# USBC-DEV-2_0.net
KiCad netlist of a schematic drawn in Altium Designer
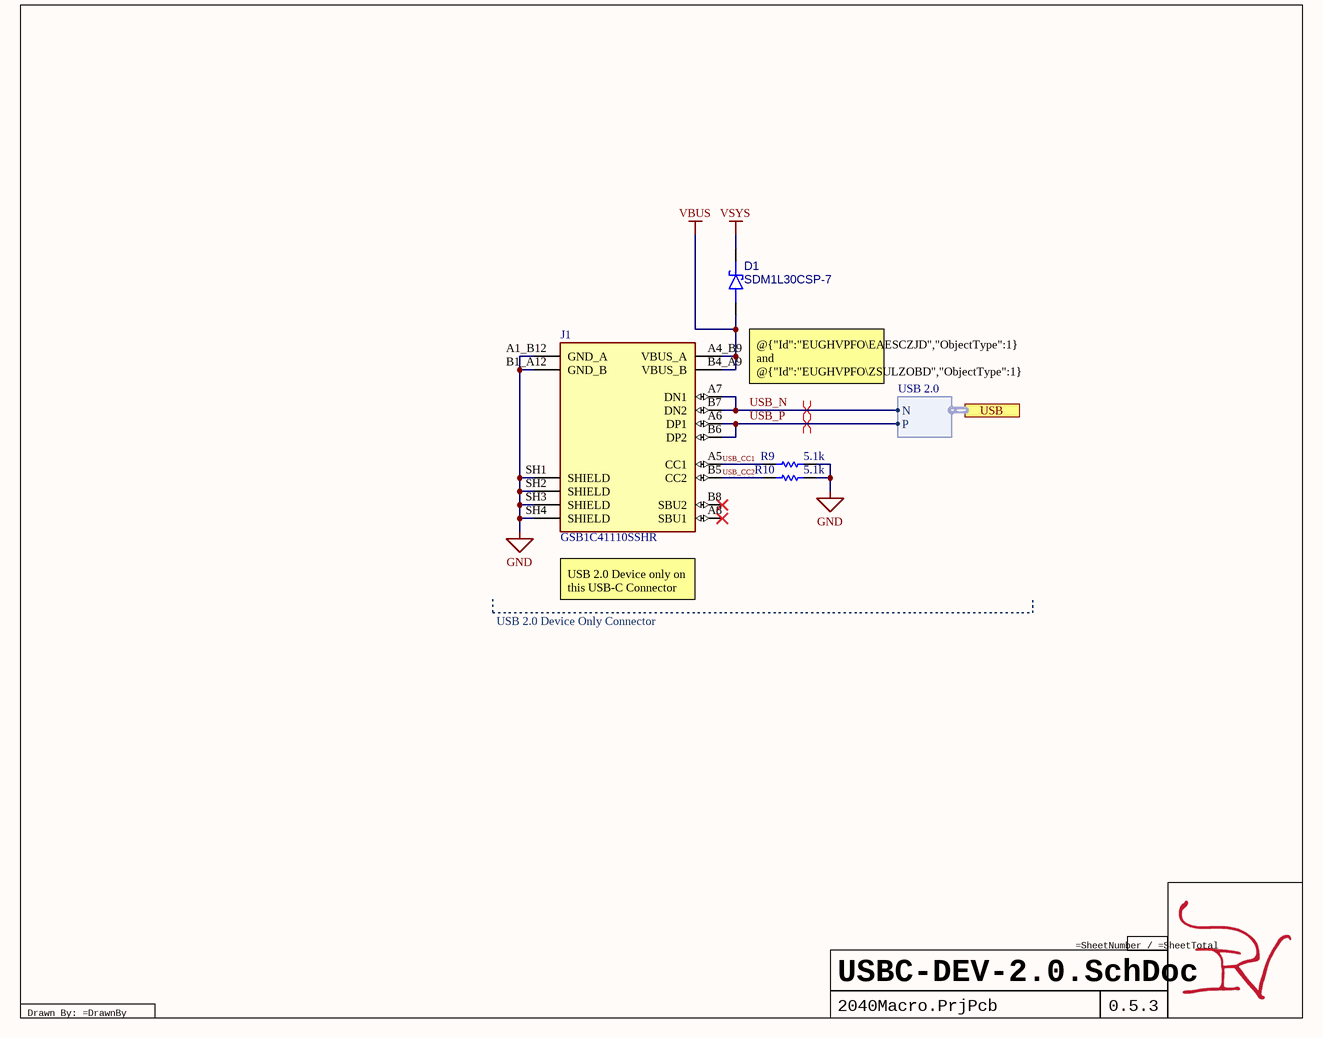
[diagram p0: USBC-DEV-2.0.SchDoc]

(export (version "E")
  (design (tool "Eeschema 10.0.6"))
  (components
    (comp (ref "D1")
      (value "SDM1L30CSP-7")
      (footprint "SDM1L30CSP-7-Footprint-1")
      (description "Rectifier Diode, Schottky, 1 Phase, 1 Element, 1A, 30V V(RRM), Silicon")
      (libsource (lib "IIT Motorsports") (part "DIODE-SKY-2"))
    )
    (comp (ref "J1")
      (value "GSB1C41110SSHR")
      (footprint "AMPHENOL_GSB1C41110SSHR")
      (description "USB2.0, Type C, Top Mount, Center Height 1.63MM, Single Row SMT")
      (fields (field (name "MF") "{'manufacturer': u'Amphenol Canada'}"))
      (libsource (lib "IIT Motorsports") (part "GSB1C41110SSHR"))
    )
    (comp (ref "R9")
      (value "5.1k")
      (footprint "RES 0201_0603")
      (fields
        (field (name "POWER") "50mW")
        (field (name "TOLERANCE") "1%")
        (field (name "Comment") "5k1-0201-0.05/1")
      )
      (libsource (lib "IIT Motorsports") (part "RES"))
    )
    (comp (ref "R10")
      (value "5.1k")
      (footprint "RES 0201_0603")
      (fields
        (field (name "POWER") "50mW")
        (field (name "TOLERANCE") "1%")
        (field (name "Comment") "5k1-0201-0.05/1")
      )
      (libsource (lib "IIT Motorsports") (part "RES"))
    )
  )
  (nets
    (net (code "3") (name "/USB_CC1") (class "Default")
      (node (ref "J1") (pin "A5") (pinfunction "CC1_A5") (pintype "bidirectional"))
      (node (ref "R9") (pin "1") (pinfunction "1_1") (pintype "passive"))
    )
    (net (code "4") (name "/USB_CC2") (class "Default")
      (node (ref "J1") (pin "B5") (pinfunction "CC2_B5") (pintype "bidirectional"))
      (node (ref "R10") (pin "1") (pinfunction "1_1") (pintype "passive"))
    )
    (net (code "5") (name "/USB_N") (class "Default")
      (node (ref "J1") (pin "A7") (pinfunction "DN1_A7") (pintype "bidirectional"))
      (node (ref "J1") (pin "B7") (pinfunction "DN2_B7") (pintype "bidirectional"))
    )
    (net (code "6") (name "/USB_P") (class "Default")
      (node (ref "J1") (pin "A6") (pinfunction "DP1_A6") (pintype "bidirectional"))
      (node (ref "J1") (pin "B6") (pinfunction "DP2_B6") (pintype "bidirectional"))
    )
    (net (code "8") (name "GND") (class "Default")
      (node (ref "J1") (pin "A1_B12") (pinfunction "GND_A_A1_B12") (pintype "power_in"))
      (node (ref "J1") (pin "B1_A12") (pinfunction "GND_B_B1_A12") (pintype "power_in"))
      (node (ref "J1") (pin "SH1") (pinfunction "SHIELD_SH1") (pintype "passive"))
      (node (ref "J1") (pin "SH2") (pinfunction "SHIELD_SH2") (pintype "passive"))
      (node (ref "J1") (pin "SH3") (pinfunction "SHIELD_SH3") (pintype "passive"))
      (node (ref "J1") (pin "SH4") (pinfunction "SHIELD_SH4") (pintype "passive"))
      (node (ref "R10") (pin "2") (pinfunction "2_2") (pintype "passive"))
      (node (ref "R9") (pin "2") (pinfunction "2_2") (pintype "passive"))
    )
    (net (code "9") (name "VBUS") (class "Default")
      (node (ref "D1") (pin "2") (pinfunction "A_2") (pintype "passive"))
      (node (ref "J1") (pin "A4_B9") (pinfunction "VBUS_A_A4_B9") (pintype "power_in"))
      (node (ref "J1") (pin "B4_A9") (pinfunction "VBUS_B_B4_A9") (pintype "power_in"))
    )
    (net (code "10") (name "VSYS") (class "Default")
      (node (ref "D1") (pin "1") (pinfunction "K_1") (pintype "passive"))
    )
    (net (code "11") (name "unconnected-(J1-SBU1-PadA8)") (class "Default")
      (node (ref "J1") (pin "A8") (pinfunction "SBU1_A8") (pintype "bidirectional+no_connect"))
    )
    (net (code "12") (name "unconnected-(J1-SBU2-PadB8)") (class "Default")
      (node (ref "J1") (pin "B8") (pinfunction "SBU2_B8") (pintype "bidirectional+no_connect"))
    )
  )
)
